# Vernier_Interface_Shield.net
KiCad netlist of a schematic drawn in EAGLE
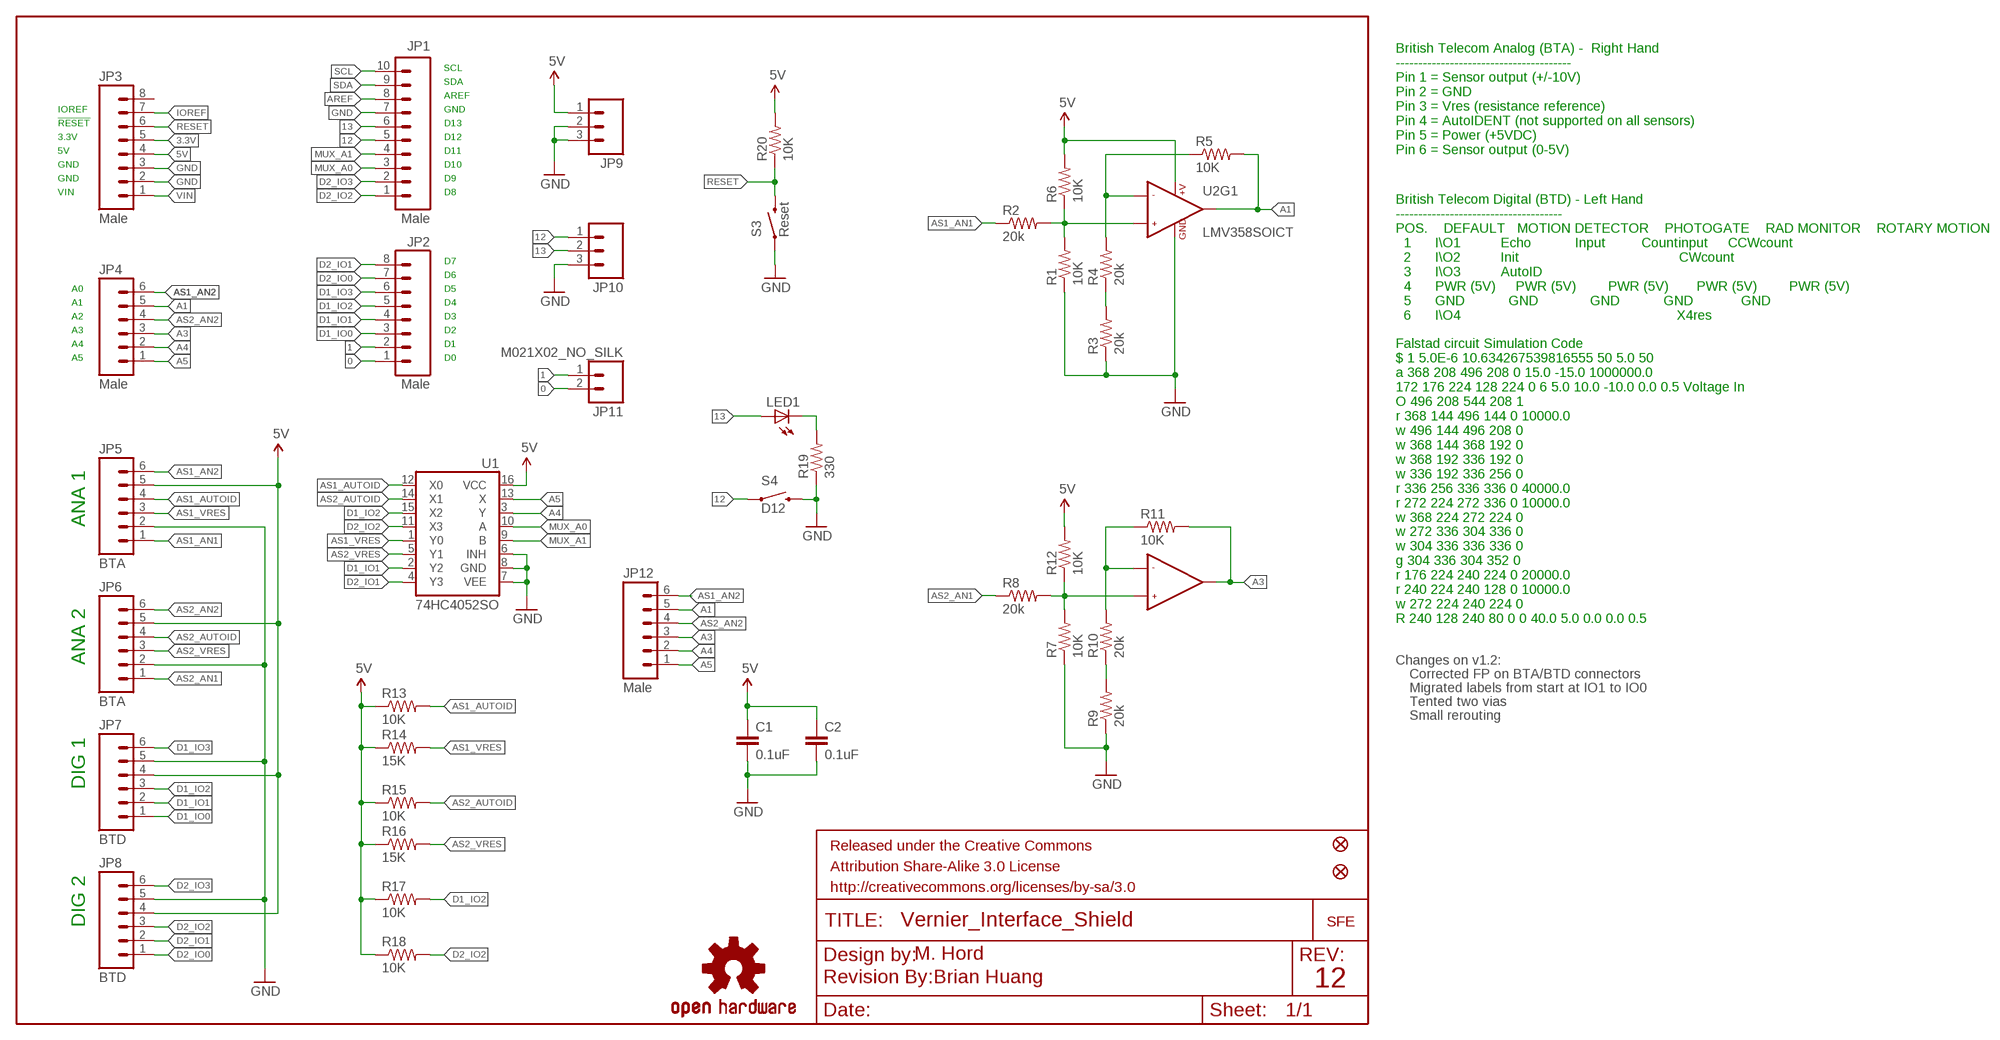
[diagram p0: schematic, sheet 1]

(export (version "E")
  (design (tool "Eeschema 10.0.6"))
  (components
    (comp (ref "C1")
      (value "0.1uF")
      (footprint "eagle-import:0603-CAP")
      (libsource (lib "eagle-import") (part "0.1UF-25V(+80/-20%)(0603)"))
    )
    (comp (ref "C2")
      (value "0.1uF")
      (footprint "eagle-import:0603-CAP")
      (libsource (lib "eagle-import") (part "0.1UF-25V(+80/-20%)(0603)"))
    )
    (comp (ref "FID1")
      (value "FIDUCIAL1X2")
      (footprint "eagle-import:FIDUCIAL-1X2")
      (libsource (lib "eagle-import") (part "FIDUCIAL1X2"))
    )
    (comp (ref "FID2")
      (value "FIDUCIAL1X2")
      (footprint "eagle-import:FIDUCIAL-1X2")
      (libsource (lib "eagle-import") (part "FIDUCIAL1X2"))
    )
    (comp (ref "FRAME1")
      (value "FRAME-LETTER")
      (footprint "eagle-import:CREATIVE_COMMONS")
      (libsource (lib "eagle-import") (part "FRAME-LETTER"))
    )
    (comp (ref "JP1")
      (value "Male")
      (footprint "eagle-import:1X10_SMD_MALE")
      (libsource (lib "eagle-import") (part "M10SMD_MALE"))
    )
    (comp (ref "JP2")
      (value "Male")
      (footprint "eagle-import:1X08_SMD_MALE")
      (libsource (lib "eagle-import") (part "M08SMD-MALE"))
    )
    (comp (ref "JP3")
      (value "Male")
      (footprint "eagle-import:1X08_SMD_MALE")
      (libsource (lib "eagle-import") (part "M08SMD-MALE"))
    )
    (comp (ref "JP4")
      (value "Male")
      (footprint "eagle-import:1X06_SMD_MALE")
      (libsource (lib "eagle-import") (part "M06SMD_MALE"))
    )
    (comp (ref "JP5")
      (value "BTA")
      (footprint "eagle-import:BTA")
      (libsource (lib "eagle-import") (part "M06VERNIER-ANALOG"))
    )
    (comp (ref "JP6")
      (value "BTA")
      (footprint "eagle-import:BTA")
      (libsource (lib "eagle-import") (part "M06VERNIER-ANALOG"))
    )
    (comp (ref "JP7")
      (value "BTD")
      (footprint "eagle-import:BTD")
      (libsource (lib "eagle-import") (part "M06VERNIER-DIGITAL"))
    )
    (comp (ref "JP8")
      (value "BTD")
      (footprint "eagle-import:BTD")
      (libsource (lib "eagle-import") (part "M06VERNIER-DIGITAL"))
    )
    (comp (ref "JP9")
      (value "M031X03_NO_SILK")
      (footprint "eagle-import:1X03_NO_SILK")
      (libsource (lib "eagle-import") (part "M031X03_NO_SILK"))
    )
    (comp (ref "JP10")
      (value "M031X03_NO_SILK")
      (footprint "eagle-import:1X03_NO_SILK")
      (libsource (lib "eagle-import") (part "M031X03_NO_SILK"))
    )
    (comp (ref "JP11")
      (value "M021X02_NO_SILK")
      (footprint "eagle-import:1X02_NO_SILK")
      (libsource (lib "eagle-import") (part "M021X02_NO_SILK"))
    )
    (comp (ref "JP12")
      (value "Male")
      (footprint "eagle-import:1X06")
      (libsource (lib "eagle-import") (part "M06SIP"))
    )
    (comp (ref "LED1")
      (value "LED5MM")
      (footprint "eagle-import:LED5MM")
      (libsource (lib "eagle-import") (part "LED5MM"))
    )
    (comp (ref "LOGO2")
      (value "OSHW-LOGOS")
      (footprint "eagle-import:OSHW-LOGO-S")
      (libsource (lib "eagle-import") (part "OSHW-LOGOS"))
    )
    (comp (ref "LOGO_1")
      (value "LOGO-SFESK")
      (footprint "eagle-import:SFE-LOGO-FLAME")
      (libsource (lib "eagle-import") (part "LOGO-SFESK"))
    )
    (comp (ref "R1")
      (value "10K")
      (footprint "eagle-import:0603-RES")
      (libsource (lib "eagle-import") (part "10KOHM1/10W1%(0603)0603"))
    )
    (comp (ref "R2")
      (value "20k")
      (footprint "eagle-import:0603-RES")
      (libsource (lib "eagle-import") (part "20KOHM1/10W1%(0603)"))
    )
    (comp (ref "R3")
      (value "20k")
      (footprint "eagle-import:0603-RES")
      (libsource (lib "eagle-import") (part "20KOHM1/10W1%(0603)"))
    )
    (comp (ref "R4")
      (value "20k")
      (footprint "eagle-import:0603-RES")
      (libsource (lib "eagle-import") (part "20KOHM1/10W1%(0603)"))
    )
    (comp (ref "R5")
      (value "10K")
      (footprint "eagle-import:0603-RES")
      (libsource (lib "eagle-import") (part "10KOHM1/10W1%(0603)0603"))
    )
    (comp (ref "R6")
      (value "10K")
      (footprint "eagle-import:0603-RES")
      (libsource (lib "eagle-import") (part "10KOHM1/10W1%(0603)0603"))
    )
    (comp (ref "R7")
      (value "10K")
      (footprint "eagle-import:0603-RES")
      (libsource (lib "eagle-import") (part "10KOHM1/10W1%(0603)0603"))
    )
    (comp (ref "R8")
      (value "20k")
      (footprint "eagle-import:0603-RES")
      (libsource (lib "eagle-import") (part "20KOHM1/10W1%(0603)"))
    )
    (comp (ref "R9")
      (value "20k")
      (footprint "eagle-import:0603-RES")
      (libsource (lib "eagle-import") (part "20KOHM1/10W1%(0603)"))
    )
    (comp (ref "R10")
      (value "20k")
      (footprint "eagle-import:0603-RES")
      (libsource (lib "eagle-import") (part "20KOHM1/10W1%(0603)"))
    )
    (comp (ref "R11")
      (value "10K")
      (footprint "eagle-import:0603-RES")
      (libsource (lib "eagle-import") (part "10KOHM1/10W1%(0603)0603"))
    )
    (comp (ref "R12")
      (value "10K")
      (footprint "eagle-import:0603-RES")
      (libsource (lib "eagle-import") (part "10KOHM1/10W1%(0603)0603"))
    )
    (comp (ref "R13")
      (value "10K")
      (footprint "eagle-import:0603-RES")
      (libsource (lib "eagle-import") (part "10KOHM1/10W1%(0603)0603"))
    )
    (comp (ref "R14")
      (value "15K")
      (footprint "eagle-import:0603-RES")
      (libsource (lib "eagle-import") (part "15KOHM1/10W1%(0603)0603"))
    )
    (comp (ref "R15")
      (value "10K")
      (footprint "eagle-import:0603-RES")
      (libsource (lib "eagle-import") (part "10KOHM1/10W1%(0603)0603"))
    )
    (comp (ref "R16")
      (value "15K")
      (footprint "eagle-import:0603-RES")
      (libsource (lib "eagle-import") (part "15KOHM1/10W1%(0603)0603"))
    )
    (comp (ref "R17")
      (value "10K")
      (footprint "eagle-import:0603-RES")
      (libsource (lib "eagle-import") (part "10KOHM1/10W1%(0603)0603"))
    )
    (comp (ref "R18")
      (value "10K")
      (footprint "eagle-import:0603-RES")
      (libsource (lib "eagle-import") (part "10KOHM1/10W1%(0603)0603"))
    )
    (comp (ref "R19")
      (value "330")
      (footprint "eagle-import:0603-RES")
      (libsource (lib "eagle-import") (part "330OHM1/10W1%(0603)"))
    )
    (comp (ref "R20")
      (value "10K")
      (footprint "eagle-import:0603-RES")
      (libsource (lib "eagle-import") (part "10KOHM1/10W1%(0603)0603"))
    )
    (comp (ref "S3")
      (value "Reset")
      (footprint "eagle-import:TACTILE-PTH")
      (libsource (lib "eagle-import") (part "SWITCH-MOMENTARY-2PTH"))
    )
    (comp (ref "S4")
      (value "D12")
      (footprint "eagle-import:TACTILE-PTH")
      (libsource (lib "eagle-import") (part "SWITCH-MOMENTARY-2PTH"))
    )
    (comp (ref "U$1")
      (value "REVISION")
      (footprint "eagle-import:REVISION")
      (libsource (lib "eagle-import") (part "REVISION"))
    )
    (comp (ref "U1")
      (value "74HC4052SO")
      (footprint "eagle-import:SO16")
      (libsource (lib "eagle-import") (part "74HC4052SO"))
    )
    (comp (ref "U2")
      (value "LMV358SOICT")
      (footprint "eagle-import:SO08-TIGHT")
      (libsource (lib "eagle-import") (part "LMV358SOICT"))
    )
  )
  (nets
    (net (code "1") (name "0") (class "Default")
      (node (ref "JP11") (pin "2") (pinfunction "2_2") (pintype "passive"))
      (node (ref "JP2") (pin "1") (pinfunction "1_1") (pintype "passive"))
    )
    (net (code "2") (name "1") (class "Default")
      (node (ref "JP11") (pin "1") (pinfunction "1_1") (pintype "passive"))
      (node (ref "JP2") (pin "2") (pinfunction "2_2") (pintype "passive"))
    )
    (net (code "3") (name "3.3V") (class "Default")
      (node (ref "JP3") (pin "5") (pinfunction "5_5") (pintype "passive"))
    )
    (net (code "4") (name "5V") (class "Default")
      (node (ref "C1") (pin "1") (pinfunction "1_1") (pintype "passive"))
      (node (ref "C2") (pin "1") (pinfunction "1_1") (pintype "passive"))
      (node (ref "JP3") (pin "4") (pinfunction "4_4") (pintype "passive"))
      (node (ref "JP5") (pin "5") (pinfunction "5_5") (pintype "passive"))
      (node (ref "JP6") (pin "5") (pinfunction "5_5") (pintype "passive"))
      (node (ref "JP7") (pin "4") (pinfunction "4_4") (pintype "passive"))
      (node (ref "JP8") (pin "4") (pinfunction "4_4") (pintype "passive"))
      (node (ref "JP9") (pin "1") (pinfunction "1_1") (pintype "passive"))
      (node (ref "R12") (pin "2") (pinfunction "2_2") (pintype "passive"))
      (node (ref "R13") (pin "1") (pinfunction "1_1") (pintype "passive"))
      (node (ref "R14") (pin "1") (pinfunction "1_1") (pintype "passive"))
      (node (ref "R15") (pin "1") (pinfunction "1_1") (pintype "passive"))
      (node (ref "R16") (pin "1") (pinfunction "1_1") (pintype "passive"))
      (node (ref "R17") (pin "1") (pinfunction "1_1") (pintype "passive"))
      (node (ref "R18") (pin "1") (pinfunction "1_1") (pintype "passive"))
      (node (ref "R20") (pin "2") (pinfunction "2_2") (pintype "passive"))
      (node (ref "R6") (pin "2") (pinfunction "2_2") (pintype "passive"))
      (node (ref "U1") (pin "16") (pinfunction "VCC_16") (pintype "power_in"))
      (node (ref "U2") (pin "8") (pinfunction "+V_8") (pintype "power_in"))
    )
    (net (code "5") (name "12") (class "Default")
      (node (ref "JP1") (pin "5") (pinfunction "5_5") (pintype "passive"))
      (node (ref "JP10") (pin "1") (pinfunction "1_1") (pintype "passive"))
      (node (ref "S4") (pin "1") (pinfunction "1_1") (pintype "passive"))
    )
    (net (code "6") (name "13") (class "Default")
      (node (ref "JP1") (pin "6") (pinfunction "6_6") (pintype "passive"))
      (node (ref "JP10") (pin "2") (pinfunction "2_2") (pintype "passive"))
      (node (ref "LED1") (pin "A") (pinfunction "A_A") (pintype "passive"))
    )
    (net (code "7") (name "A1") (class "Default")
      (node (ref "JP12") (pin "5") (pinfunction "5_5") (pintype "passive"))
      (node (ref "JP4") (pin "5") (pinfunction "5_5") (pintype "passive"))
      (node (ref "R5") (pin "2") (pinfunction "2_2") (pintype "passive"))
      (node (ref "U2") (pin "1") (pinfunction "OUT1_1") (pintype "output"))
    )
    (net (code "8") (name "A3") (class "Default")
      (node (ref "JP12") (pin "3") (pinfunction "3_3") (pintype "passive"))
      (node (ref "JP4") (pin "3") (pinfunction "3_3") (pintype "passive"))
      (node (ref "R11") (pin "2") (pinfunction "2_2") (pintype "passive"))
      (node (ref "U2") (pin "7") (pinfunction "OUT2_7") (pintype "output"))
    )
    (net (code "9") (name "A4") (class "Default")
      (node (ref "JP12") (pin "2") (pinfunction "2_2") (pintype "passive"))
      (node (ref "JP4") (pin "2") (pinfunction "2_2") (pintype "passive"))
      (node (ref "U1") (pin "3") (pinfunction "Y_3") (pintype "bidirectional"))
    )
    (net (code "10") (name "A5") (class "Default")
      (node (ref "JP12") (pin "1") (pinfunction "1_1") (pintype "passive"))
      (node (ref "JP4") (pin "1") (pinfunction "1_1") (pintype "passive"))
      (node (ref "U1") (pin "13") (pinfunction "X_13") (pintype "bidirectional"))
    )
    (net (code "11") (name "AREF") (class "Default")
      (node (ref "JP1") (pin "8") (pinfunction "8_8") (pintype "passive"))
    )
    (net (code "12") (name "AS1_AN1") (class "Default")
      (node (ref "JP5") (pin "1") (pinfunction "1_1") (pintype "passive"))
      (node (ref "R2") (pin "1") (pinfunction "1_1") (pintype "passive"))
    )
    (net (code "13") (name "AS1_AN2") (class "Default")
      (node (ref "JP12") (pin "6") (pinfunction "6_6") (pintype "passive"))
      (node (ref "JP4") (pin "6") (pinfunction "6_6") (pintype "passive"))
      (node (ref "JP5") (pin "6") (pinfunction "6_6") (pintype "passive"))
    )
    (net (code "14") (name "AS1_AUTOID") (class "Default")
      (node (ref "JP5") (pin "4") (pinfunction "4_4") (pintype "passive"))
      (node (ref "R13") (pin "2") (pinfunction "2_2") (pintype "passive"))
      (node (ref "U1") (pin "12") (pinfunction "X0_12") (pintype "bidirectional"))
    )
    (net (code "15") (name "AS1_VRES") (class "Default")
      (node (ref "JP5") (pin "3") (pinfunction "3_3") (pintype "passive"))
      (node (ref "R14") (pin "2") (pinfunction "2_2") (pintype "passive"))
      (node (ref "U1") (pin "1") (pinfunction "Y0_1") (pintype "bidirectional"))
    )
    (net (code "16") (name "AS2_AN1") (class "Default")
      (node (ref "JP6") (pin "1") (pinfunction "1_1") (pintype "passive"))
      (node (ref "R8") (pin "1") (pinfunction "1_1") (pintype "passive"))
    )
    (net (code "17") (name "AS2_AN2") (class "Default")
      (node (ref "JP12") (pin "4") (pinfunction "4_4") (pintype "passive"))
      (node (ref "JP4") (pin "4") (pinfunction "4_4") (pintype "passive"))
      (node (ref "JP6") (pin "6") (pinfunction "6_6") (pintype "passive"))
    )
    (net (code "18") (name "AS2_AUTOID") (class "Default")
      (node (ref "JP6") (pin "4") (pinfunction "4_4") (pintype "passive"))
      (node (ref "R15") (pin "2") (pinfunction "2_2") (pintype "passive"))
      (node (ref "U1") (pin "14") (pinfunction "X1_14") (pintype "bidirectional"))
    )
    (net (code "19") (name "AS2_VRES") (class "Default")
      (node (ref "JP6") (pin "3") (pinfunction "3_3") (pintype "passive"))
      (node (ref "R16") (pin "2") (pinfunction "2_2") (pintype "passive"))
      (node (ref "U1") (pin "5") (pinfunction "Y1_5") (pintype "bidirectional"))
    )
    (net (code "20") (name "D1_IO0") (class "Default")
      (node (ref "JP2") (pin "3") (pinfunction "3_3") (pintype "passive"))
      (node (ref "JP7") (pin "1") (pinfunction "1_1") (pintype "passive"))
    )
    (net (code "21") (name "D1_IO1") (class "Default")
      (node (ref "JP2") (pin "4") (pinfunction "4_4") (pintype "passive"))
      (node (ref "JP7") (pin "2") (pinfunction "2_2") (pintype "passive"))
      (node (ref "U1") (pin "2") (pinfunction "Y2_2") (pintype "bidirectional"))
    )
    (net (code "22") (name "D1_IO2") (class "Default")
      (node (ref "JP2") (pin "5") (pinfunction "5_5") (pintype "passive"))
      (node (ref "JP7") (pin "3") (pinfunction "3_3") (pintype "passive"))
      (node (ref "R17") (pin "2") (pinfunction "2_2") (pintype "passive"))
      (node (ref "U1") (pin "15") (pinfunction "X2_15") (pintype "bidirectional"))
    )
    (net (code "23") (name "D1_IO3") (class "Default")
      (node (ref "JP2") (pin "6") (pinfunction "6_6") (pintype "passive"))
      (node (ref "JP7") (pin "6") (pinfunction "6_6") (pintype "passive"))
    )
    (net (code "24") (name "D2_IO0") (class "Default")
      (node (ref "JP2") (pin "7") (pinfunction "7_7") (pintype "passive"))
      (node (ref "JP8") (pin "1") (pinfunction "1_1") (pintype "passive"))
    )
    (net (code "25") (name "D2_IO1") (class "Default")
      (node (ref "JP2") (pin "8") (pinfunction "8_8") (pintype "passive"))
      (node (ref "JP8") (pin "2") (pinfunction "2_2") (pintype "passive"))
      (node (ref "U1") (pin "4") (pinfunction "Y3_4") (pintype "bidirectional"))
    )
    (net (code "26") (name "D2_IO2") (class "Default")
      (node (ref "JP1") (pin "1") (pinfunction "1_1") (pintype "passive"))
      (node (ref "JP8") (pin "3") (pinfunction "3_3") (pintype "passive"))
      (node (ref "R18") (pin "2") (pinfunction "2_2") (pintype "passive"))
      (node (ref "U1") (pin "11") (pinfunction "X3_11") (pintype "bidirectional"))
    )
    (net (code "27") (name "D2_IO3") (class "Default")
      (node (ref "JP1") (pin "2") (pinfunction "2_2") (pintype "passive"))
      (node (ref "JP8") (pin "6") (pinfunction "6_6") (pintype "passive"))
    )
    (net (code "28") (name "GND") (class "Default")
      (node (ref "C1") (pin "2") (pinfunction "2_2") (pintype "passive"))
      (node (ref "C2") (pin "2") (pinfunction "2_2") (pintype "passive"))
      (node (ref "JP1") (pin "7") (pinfunction "7_7") (pintype "passive"))
      (node (ref "JP10") (pin "3") (pinfunction "3_3") (pintype "passive"))
      (node (ref "JP3") (pin "2") (pinfunction "2_2") (pintype "passive"))
      (node (ref "JP3") (pin "3") (pinfunction "3_3") (pintype "passive"))
      (node (ref "JP5") (pin "2") (pinfunction "2_2") (pintype "passive"))
      (node (ref "JP6") (pin "2") (pinfunction "2_2") (pintype "passive"))
      (node (ref "JP7") (pin "5") (pinfunction "5_5") (pintype "passive"))
      (node (ref "JP8") (pin "5") (pinfunction "5_5") (pintype "passive"))
      (node (ref "JP9") (pin "2") (pinfunction "2_2") (pintype "passive"))
      (node (ref "JP9") (pin "3") (pinfunction "3_3") (pintype "passive"))
      (node (ref "R1") (pin "1") (pinfunction "1_1") (pintype "passive"))
      (node (ref "R19") (pin "1") (pinfunction "1_1") (pintype "passive"))
      (node (ref "R3") (pin "1") (pinfunction "1_1") (pintype "passive"))
      (node (ref "R7") (pin "1") (pinfunction "1_1") (pintype "passive"))
      (node (ref "R9") (pin "1") (pinfunction "1_1") (pintype "passive"))
      (node (ref "S3") (pin "1") (pinfunction "1_1") (pintype "passive"))
      (node (ref "S4") (pin "3") (pinfunction "2_3") (pintype "passive"))
      (node (ref "U1") (pin "6") (pinfunction "INH_6") (pintype "input"))
      (node (ref "U1") (pin "7") (pinfunction "VEE_7") (pintype "power_in"))
      (node (ref "U1") (pin "8") (pinfunction "GND_8") (pintype "power_in"))
      (node (ref "U2") (pin "4") (pinfunction "GND_4") (pintype "power_in"))
    )
    (net (code "29") (name "IOREF") (class "Default")
      (node (ref "JP3") (pin "7") (pinfunction "7_7") (pintype "passive"))
    )
    (net (code "30") (name "MUX_A0") (class "Default")
      (node (ref "JP1") (pin "3") (pinfunction "3_3") (pintype "passive"))
      (node (ref "U1") (pin "10") (pinfunction "A_10") (pintype "input"))
    )
    (net (code "31") (name "MUX_A1") (class "Default")
      (node (ref "JP1") (pin "4") (pinfunction "4_4") (pintype "passive"))
      (node (ref "U1") (pin "9") (pinfunction "B_9") (pintype "input"))
    )
    (net (code "32") (name "Net-(LED1-C)") (class "Default")
      (node (ref "LED1") (pin "K") (pinfunction "C_K") (pintype "passive"))
      (node (ref "R19") (pin "2") (pinfunction "2_2") (pintype "passive"))
    )
    (net (code "33") (name "Net-(R3-Pad2)") (class "Default")
      (node (ref "R3") (pin "2") (pinfunction "2_2") (pintype "passive"))
      (node (ref "R4") (pin "1") (pinfunction "1_1") (pintype "passive"))
    )
    (net (code "34") (name "Net-(R10-Pad1)") (class "Default")
      (node (ref "R10") (pin "1") (pinfunction "1_1") (pintype "passive"))
      (node (ref "R9") (pin "2") (pinfunction "2_2") (pintype "passive"))
    )
    (net (code "35") (name "Net-(U2A-+IN1)") (class "Default")
      (node (ref "R1") (pin "2") (pinfunction "2_2") (pintype "passive"))
      (node (ref "R2") (pin "2") (pinfunction "2_2") (pintype "passive"))
      (node (ref "R6") (pin "1") (pinfunction "1_1") (pintype "passive"))
      (node (ref "U2") (pin "3") (pinfunction "+IN1_3") (pintype "input"))
    )
    (net (code "36") (name "Net-(U2A--IN1)") (class "Default")
      (node (ref "R4") (pin "2") (pinfunction "2_2") (pintype "passive"))
      (node (ref "R5") (pin "1") (pinfunction "1_1") (pintype "passive"))
      (node (ref "U2") (pin "2") (pinfunction "-IN1_2") (pintype "input"))
    )
    (net (code "37") (name "Net-(U2B-+IN2)") (class "Default")
      (node (ref "R12") (pin "1") (pinfunction "1_1") (pintype "passive"))
      (node (ref "R7") (pin "2") (pinfunction "2_2") (pintype "passive"))
      (node (ref "R8") (pin "2") (pinfunction "2_2") (pintype "passive"))
      (node (ref "U2") (pin "5") (pinfunction "+IN2_5") (pintype "input"))
    )
    (net (code "38") (name "Net-(U2B--IN2)") (class "Default")
      (node (ref "R10") (pin "2") (pinfunction "2_2") (pintype "passive"))
      (node (ref "R11") (pin "1") (pinfunction "1_1") (pintype "passive"))
      (node (ref "U2") (pin "6") (pinfunction "-IN2_6") (pintype "input"))
    )
    (net (code "39") (name "RESET") (class "Default")
      (node (ref "JP3") (pin "6") (pinfunction "6_6") (pintype "passive"))
      (node (ref "R20") (pin "1") (pinfunction "1_1") (pintype "passive"))
      (node (ref "S3") (pin "3") (pinfunction "2_3") (pintype "passive"))
    )
    (net (code "40") (name "SCL") (class "Default")
      (node (ref "JP1") (pin "10") (pinfunction "10_10") (pintype "passive"))
    )
    (net (code "41") (name "SDA") (class "Default")
      (node (ref "JP1") (pin "9") (pinfunction "9_9") (pintype "passive"))
    )
    (net (code "42") (name "VIN") (class "Default")
      (node (ref "JP3") (pin "1") (pinfunction "1_1") (pintype "passive"))
    )
    (net (code "43") (name "unconnected-(JP3-Pad8)") (class "Default")
      (node (ref "JP3") (pin "8") (pinfunction "8_8") (pintype "passive"))
    )
  )
)
